# pixracer_serials.net
KiCad netlist of a schematic drawn in Altium Designer
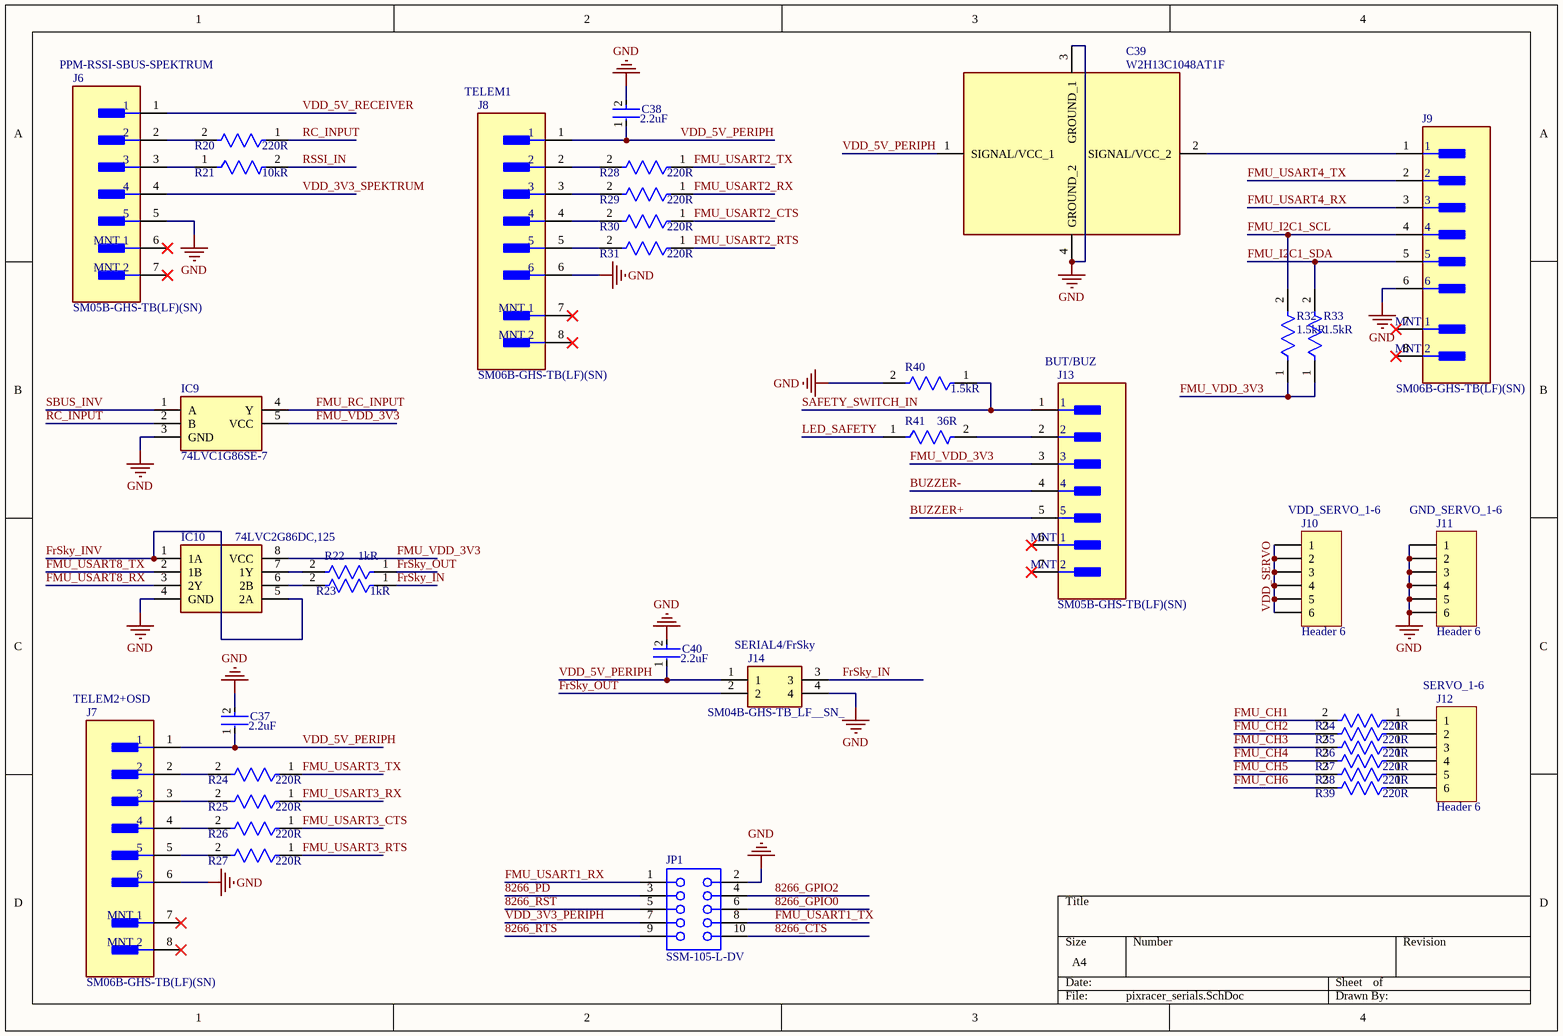
[diagram p0: pixracer_serials.SchDoc]

(export (version "E")
  (design (tool "Eeschema 10.0.6"))
  (components
    (comp (ref "C37")
      (value "C1608X7R1A225K080AC")
      (footprint "FP-C1608-080-0_1-MFG")
      (description "Multilayer Ceramic Capacitors 2.2μF ±10% 10V X7R SMD 0603")
      (fields (field (name "CAPACITANCE") "2.2uF") (field (name "TOLERANCE") "10%"))
      (libsource (lib "Altium Content Vault") (part "236180d848d6139a670b325ea6854c9"))
    )
    (comp (ref "C38")
      (value "C1608X7R1A225K080AC")
      (footprint "FP-C1608-080-0_1-MFG")
      (description "Multilayer Ceramic Capacitors 2.2μF ±10% 10V X7R SMD 0603")
      (fields (field (name "CAPACITANCE") "2.2uF") (field (name "TOLERANCE") "10%"))
      (libsource (lib "Altium Content Vault") (part "236180d848d6139a670b325ea6854c9"))
    )
    (comp (ref "C39")
      (value "W2H13C1048AT1F")
      (footprint "SamacSys:W2H13C1048AT1A")
      (description "Capacitor")
      (fields (field (name "MOUSER PART NUMBER") "581-W2H13C1048AT1F"))
      (libsource (lib "*") (part "W2H13C1048AT1F"))
    )
    (comp (ref "C40")
      (value "C1608X7R1A225K080AC")
      (footprint "FP-C1608-080-0_1-MFG")
      (description "Multilayer Ceramic Capacitors 2.2μF ±10% 10V X7R SMD 0603")
      (fields (field (name "CAPACITANCE") "2.2uF") (field (name "TOLERANCE") "10%"))
      (libsource (lib "Altium Content Vault") (part "236180d848d6139a670b325ea6854c9"))
    )
    (comp (ref "IC9")
      (value "74LVC1G86SE-7")
      (footprint "SamacSys:SOT65P210X110-5N")
      (description "Integrated Circuit")
      (fields (field (name "MOUSER PART NUMBER") "621-74LVC1G86SE-7"))
      (libsource (lib "*") (part "74LVC1G86SE-7"))
    )
    (comp (ref "IC10")
      (value "74LVC2G86DC,125")
      (footprint "SamacSys:SOP50P310X100-8N")
      (description "Integrated Circuit")
      (fields (field (name "MOUSER PART NUMBER") "771-LVC2G86DC125"))
      (libsource (lib "*") (part "74LVC2G86DC,125"))
    )
    (comp (ref "J6")
      (value "SM05B-GHS-TB(LF)(SN)")
      (footprint "FP-SM05B-GHS-TB_LF_SN-MFG")
      (description "CONN HEADER SMD R/A 5POS 1.25MM")
      (libsource (lib "Altium Content Vault") (part "8ab9848ea90b119fa28a5ddc5abf419"))
    )
    (comp (ref "J7")
      (value "SM06B-GHS-TB(LF)(SN)")
      (footprint "FP-SM06B-GHS-TB_LF_SN-MFG")
      (description "CONN HEADER SMD R/A 6POS 1.25MM")
      (libsource (lib "Altium Content Vault") (part "ed24c53d9ba001d1a2a686240a95171"))
    )
    (comp (ref "J8")
      (value "SM06B-GHS-TB(LF)(SN)")
      (footprint "FP-SM06B-GHS-TB_LF_SN-MFG")
      (description "CONN HEADER SMD R/A 6POS 1.25MM")
      (libsource (lib "Altium Content Vault") (part "ed24c53d9ba001d1a2a686240a95171"))
    )
    (comp (ref "J9")
      (value "SM06B-GHS-TB(LF)(SN)")
      (footprint "FP-SM06B-GHS-TB_LF_SN-MFG")
      (description "CONN HEADER SMD R/A 6POS 1.25MM")
      (libsource (lib "") (part "ed24c53d9ba001d1a2a686240a95171_1"))
    )
    (comp (ref "J10")
      (value "Header 6")
      (footprint "HDR1X6")
      (description "Header, 6-Pin")
      (fields (field (name "PUBLISHER") "Altium Limited"))
      (libsource (lib "Miscellaneous Connectors") (part "Header 6"))
    )
    (comp (ref "J11")
      (value "Header 6")
      (footprint "HDR1X6")
      (description "Header, 6-Pin")
      (fields (field (name "PUBLISHER") "Altium Limited"))
      (libsource (lib "Miscellaneous Connectors") (part "Header 6"))
    )
    (comp (ref "J12")
      (value "Header 6")
      (footprint "HDR1X6")
      (description "Header, 6-Pin")
      (fields (field (name "PUBLISHER") "Altium Limited"))
      (libsource (lib "Miscellaneous Connectors") (part "Header 6"))
    )
    (comp (ref "J13")
      (value "SM05B-GHS-TB(LF)(SN)")
      (footprint "FP-SM05B-GHS-TB_LF_SN-MFG")
      (description "CONN HEADER SMD R/A 5POS 1.25MM")
      (libsource (lib "") (part "8ab9848ea90b119fa28a5ddc5abf419_1"))
    )
    (comp (ref "J14")
      (value "SM04B-GHS-TB_LF__SN_")
      (footprint "SamacSys:SM04B-GHS-TB")
      (description "Connector")
      (fields (field (name "MANUFACTURER_PART_NUMBER") "SM04B-GHS-TB(LF)(SN)"))
      (libsource (lib "*") (part "SM04B-GHS-TB_LF__SN_"))
    )
    (comp (ref "JP1")
      (value "SSM-105-L-DV")
      (footprint "SMTC-SSM-105-X-DV")
      (fields (field (name "MANUFACTURER") "Samtec"))
      (libsource (lib "Altium Content Vault") (part "SMTC-SSM-105-X-DV"))
    )
    (comp (ref "R20")
      (value "CRCW0603220RFKEB")
      (footprint "FP-CRCW0603-e3-MFG")
      (description "RES Thick Film, 220Ω, 1%, 0.1W, 100ppm/°C, 0603")
      (fields (field (name "TOLERANCE") "1%") (field (name "RESISTANCE") "220R"))
      (libsource (lib "Altium Content Vault") (part "1029c3af85768c4190bb7ad29bc67b5"))
    )
    (comp (ref "R21")
      (value "ERJ-3GEYJ103V")
      (footprint "FP-ERJ3G-IPC_C")
      (description "RES SMD 10K OHM 5% 1/10W 0603")
      (fields (field (name "TOLERANCE") "5%") (field (name "RESISTANCE") "10kR"))
      (libsource (lib "Altium Content Vault") (part "1029c3af85768c4190bb7ad29bc67b5"))
    )
    (comp (ref "R22")
      (value "RC1608J102CS")
      (footprint "FP-RC1608-IPC_A")
      (description "Res Thick Film 0603 1kΩ 5% 0.1W ±100ppm/°C Molded SMD T/R")
      (fields (field (name "RESISTANCE") "1kR") (field (name "TOLERANCE") "5%"))
      (libsource (lib "Altium Content Vault") (part "1029c3af85768c4190bb7ad29bc67b5"))
    )
    (comp (ref "R23")
      (value "RC1608J102CS")
      (footprint "FP-RC1608-IPC_A")
      (description "Res Thick Film 0603 1kΩ 5% 0.1W ±100ppm/°C Molded SMD T/R")
      (fields (field (name "RESISTANCE") "1kR") (field (name "TOLERANCE") "5%"))
      (libsource (lib "Altium Content Vault") (part "1029c3af85768c4190bb7ad29bc67b5"))
    )
    (comp (ref "R24")
      (value "CRCW0603220RFKEB")
      (footprint "FP-CRCW0603-e3-MFG")
      (description "RES Thick Film, 220Ω, 1%, 0.1W, 100ppm/°C, 0603")
      (fields (field (name "TOLERANCE") "1%") (field (name "RESISTANCE") "220R"))
      (libsource (lib "Altium Content Vault") (part "1029c3af85768c4190bb7ad29bc67b5"))
    )
    (comp (ref "R25")
      (value "CRCW0603220RFKEB")
      (footprint "FP-CRCW0603-e3-MFG")
      (description "RES Thick Film, 220Ω, 1%, 0.1W, 100ppm/°C, 0603")
      (fields (field (name "TOLERANCE") "1%") (field (name "RESISTANCE") "220R"))
      (libsource (lib "Altium Content Vault") (part "1029c3af85768c4190bb7ad29bc67b5"))
    )
    (comp (ref "R26")
      (value "CRCW0603220RFKEB")
      (footprint "FP-CRCW0603-e3-MFG")
      (description "RES Thick Film, 220Ω, 1%, 0.1W, 100ppm/°C, 0603")
      (fields (field (name "TOLERANCE") "1%") (field (name "RESISTANCE") "220R"))
      (libsource (lib "Altium Content Vault") (part "1029c3af85768c4190bb7ad29bc67b5"))
    )
    (comp (ref "R27")
      (value "CRCW0603220RFKEB")
      (footprint "FP-CRCW0603-e3-MFG")
      (description "RES Thick Film, 220Ω, 1%, 0.1W, 100ppm/°C, 0603")
      (fields (field (name "TOLERANCE") "1%") (field (name "RESISTANCE") "220R"))
      (libsource (lib "Altium Content Vault") (part "1029c3af85768c4190bb7ad29bc67b5"))
    )
    (comp (ref "R28")
      (value "CRCW0603220RFKEB")
      (footprint "FP-CRCW0603-e3-MFG")
      (description "RES Thick Film, 220Ω, 1%, 0.1W, 100ppm/°C, 0603")
      (fields (field (name "TOLERANCE") "1%") (field (name "RESISTANCE") "220R"))
      (libsource (lib "Altium Content Vault") (part "1029c3af85768c4190bb7ad29bc67b5"))
    )
    (comp (ref "R29")
      (value "CRCW0603220RFKEB")
      (footprint "FP-CRCW0603-e3-MFG")
      (description "RES Thick Film, 220Ω, 1%, 0.1W, 100ppm/°C, 0603")
      (fields (field (name "TOLERANCE") "1%") (field (name "RESISTANCE") "220R"))
      (libsource (lib "Altium Content Vault") (part "1029c3af85768c4190bb7ad29bc67b5"))
    )
    (comp (ref "R30")
      (value "CRCW0603220RFKEB")
      (footprint "FP-CRCW0603-e3-MFG")
      (description "RES Thick Film, 220Ω, 1%, 0.1W, 100ppm/°C, 0603")
      (fields (field (name "TOLERANCE") "1%") (field (name "RESISTANCE") "220R"))
      (libsource (lib "Altium Content Vault") (part "1029c3af85768c4190bb7ad29bc67b5"))
    )
    (comp (ref "R31")
      (value "CRCW0603220RFKEB")
      (footprint "FP-CRCW0603-e3-MFG")
      (description "RES Thick Film, 220Ω, 1%, 0.1W, 100ppm/°C, 0603")
      (fields (field (name "TOLERANCE") "1%") (field (name "RESISTANCE") "220R"))
      (libsource (lib "Altium Content Vault") (part "1029c3af85768c4190bb7ad29bc67b5"))
    )
    (comp (ref "R32")
      (value "1.5kR")
      (footprint "FP-CPF0603-MFG")
      (description "RES SMD 1.5KΩ 0.1% 1/16W 0603")
      (fields
        (field (name "MANUFACTURER PART NUMBER") "CPF0603B1K5E1")
        (field (name "OCTOPART") "https://octopart.com/cpf0603b1k5e1-te+connectivity-9539421")
      )
      (libsource (lib "Altium Content Vault") (part "1029c3af85768c4190bb7ad29bc67b5"))
    )
    (comp (ref "R33")
      (value "1.5kR")
      (footprint "FP-CPF0603-MFG")
      (description "RES SMD 1.5KΩ 0.1% 1/16W 0603")
      (fields
        (field (name "MANUFACTURER PART NUMBER") "CPF0603B1K5E1")
        (field (name "OCTOPART") "https://octopart.com/cpf0603b1k5e1-te+connectivity-9539421")
      )
      (libsource (lib "Altium Content Vault") (part "1029c3af85768c4190bb7ad29bc67b5"))
    )
    (comp (ref "R34")
      (value "CRCW0603220RFKEB")
      (footprint "FP-CRCW0603-e3-MFG")
      (description "RES Thick Film, 220Ω, 1%, 0.1W, 100ppm/°C, 0603")
      (fields (field (name "TOLERANCE") "1%") (field (name "RESISTANCE") "220R"))
      (libsource (lib "Altium Content Vault") (part "1029c3af85768c4190bb7ad29bc67b5"))
    )
    (comp (ref "R35")
      (value "CRCW0603220RFKEB")
      (footprint "FP-CRCW0603-e3-MFG")
      (description "RES Thick Film, 220Ω, 1%, 0.1W, 100ppm/°C, 0603")
      (fields (field (name "TOLERANCE") "1%") (field (name "RESISTANCE") "220R"))
      (libsource (lib "Altium Content Vault") (part "1029c3af85768c4190bb7ad29bc67b5"))
    )
    (comp (ref "R36")
      (value "CRCW0603220RFKEB")
      (footprint "FP-CRCW0603-e3-MFG")
      (description "RES Thick Film, 220Ω, 1%, 0.1W, 100ppm/°C, 0603")
      (fields (field (name "TOLERANCE") "1%") (field (name "RESISTANCE") "220R"))
      (libsource (lib "Altium Content Vault") (part "1029c3af85768c4190bb7ad29bc67b5"))
    )
    (comp (ref "R37")
      (value "CRCW0603220RFKEB")
      (footprint "FP-CRCW0603-e3-MFG")
      (description "RES Thick Film, 220Ω, 1%, 0.1W, 100ppm/°C, 0603")
      (fields (field (name "TOLERANCE") "1%") (field (name "RESISTANCE") "220R"))
      (libsource (lib "Altium Content Vault") (part "1029c3af85768c4190bb7ad29bc67b5"))
    )
    (comp (ref "R38")
      (value "CRCW0603220RFKEB")
      (footprint "FP-CRCW0603-e3-MFG")
      (description "RES Thick Film, 220Ω, 1%, 0.1W, 100ppm/°C, 0603")
      (fields (field (name "TOLERANCE") "1%") (field (name "RESISTANCE") "220R"))
      (libsource (lib "Altium Content Vault") (part "1029c3af85768c4190bb7ad29bc67b5"))
    )
    (comp (ref "R39")
      (value "CRCW0603220RFKEB")
      (footprint "FP-CRCW0603-e3-MFG")
      (description "RES Thick Film, 220Ω, 1%, 0.1W, 100ppm/°C, 0603")
      (fields (field (name "TOLERANCE") "1%") (field (name "RESISTANCE") "220R"))
      (libsource (lib "Altium Content Vault") (part "1029c3af85768c4190bb7ad29bc67b5"))
    )
    (comp (ref "R40")
      (value "MCR03EZPFX1501")
      (footprint "FP-MCR03-IPC_A")
      (description "Thick Film Chip Resistor, 0603, 1.5kΩ, 1%, 100ppm/°C, 0.1W, 50V")
      (fields (field (name "RESISTANCE") "1.5kR") (field (name "TOLERANCE") "1%"))
      (libsource (lib "Altium Content Vault") (part "1029c3af85768c4190bb7ad29bc67b5"))
    )
    (comp (ref "R41")
      (value "CRCW060336R0JNEA")
      (footprint "FP-CRCW0603-e3-IPC_B")
      (description "RES Thick Film, 36Ω, 5%, 0.1W, 200ppm/°C, 0603")
      (fields (field (name "RESISTANCE") "36R") (field (name "TOLERANCE") "5%"))
      (libsource (lib "Altium Content Vault") (part "1029c3af85768c4190bb7ad29bc67b5"))
    )
  )
  (nets
    (net (code "1") (name "/8266_CTS") (class "Default")
      (node (ref "JP1") (pin "10") (pinfunction "10_10") (pintype "passive"))
    )
    (net (code "2") (name "/8266_GPIO0") (class "Default")
      (node (ref "JP1") (pin "6") (pinfunction "6_6") (pintype "passive"))
    )
    (net (code "3") (name "/8266_GPIO2") (class "Default")
      (node (ref "JP1") (pin "4") (pinfunction "4_4") (pintype "passive"))
    )
    (net (code "4") (name "/8266_PD") (class "Default")
      (node (ref "JP1") (pin "3") (pinfunction "3_3") (pintype "passive"))
    )
    (net (code "5") (name "/8266_RST") (class "Default")
      (node (ref "JP1") (pin "5") (pinfunction "5_5") (pintype "passive"))
    )
    (net (code "6") (name "/8266_RTS") (class "Default")
      (node (ref "JP1") (pin "9") (pinfunction "9_9") (pintype "passive"))
    )
    (net (code "7") (name "/BUZZER+") (class "Default")
      (node (ref "J13") (pin "5") (pinfunction "5_5") (pintype "passive"))
    )
    (net (code "8") (name "/BUZZER-") (class "Default")
      (node (ref "J13") (pin "4") (pinfunction "4_4") (pintype "passive"))
    )
    (net (code "9") (name "/FMU_CH1") (class "Default")
      (node (ref "R34") (pin "2") (pinfunction "2_2") (pintype "passive"))
    )
    (net (code "10") (name "/FMU_CH2") (class "Default")
      (node (ref "R35") (pin "2") (pinfunction "2_2") (pintype "passive"))
    )
    (net (code "11") (name "/FMU_CH3") (class "Default")
      (node (ref "R36") (pin "2") (pinfunction "2_2") (pintype "passive"))
    )
    (net (code "12") (name "/FMU_CH4") (class "Default")
      (node (ref "R37") (pin "2") (pinfunction "2_2") (pintype "passive"))
    )
    (net (code "13") (name "/FMU_CH5") (class "Default")
      (node (ref "R38") (pin "2") (pinfunction "2_2") (pintype "passive"))
    )
    (net (code "14") (name "/FMU_CH6") (class "Default")
      (node (ref "R39") (pin "2") (pinfunction "2_2") (pintype "passive"))
    )
    (net (code "15") (name "/FMU_I2C1_SCL") (class "Default")
      (node (ref "J9") (pin "4") (pinfunction "4_4") (pintype "passive"))
      (node (ref "R32") (pin "2") (pinfunction "2_2") (pintype "passive"))
    )
    (net (code "16") (name "/FMU_I2C1_SDA") (class "Default")
      (node (ref "J9") (pin "5") (pinfunction "5_5") (pintype "passive"))
      (node (ref "R33") (pin "2") (pinfunction "2_2") (pintype "passive"))
    )
    (net (code "17") (name "/FMU_RC_INPUT") (class "Default")
      (node (ref "IC9") (pin "4") (pinfunction "Y_4") (pintype "passive"))
    )
    (net (code "18") (name "/FMU_USART1_RX") (class "Default")
      (node (ref "JP1") (pin "1") (pinfunction "1_1") (pintype "passive"))
    )
    (net (code "19") (name "/FMU_USART1_TX") (class "Default")
      (node (ref "JP1") (pin "8") (pinfunction "8_8") (pintype "passive"))
    )
    (net (code "20") (name "/FMU_USART2_CTS") (class "Default")
      (node (ref "R30") (pin "1") (pinfunction "1_1") (pintype "passive"))
    )
    (net (code "21") (name "/FMU_USART2_RTS") (class "Default")
      (node (ref "R31") (pin "1") (pinfunction "1_1") (pintype "passive"))
    )
    (net (code "22") (name "/FMU_USART2_RX") (class "Default")
      (node (ref "R29") (pin "1") (pinfunction "1_1") (pintype "passive"))
    )
    (net (code "23") (name "/FMU_USART2_TX") (class "Default")
      (node (ref "R28") (pin "1") (pinfunction "1_1") (pintype "passive"))
    )
    (net (code "24") (name "/FMU_USART3_CTS") (class "Default")
      (node (ref "R26") (pin "1") (pinfunction "1_1") (pintype "passive"))
    )
    (net (code "25") (name "/FMU_USART3_RTS") (class "Default")
      (node (ref "R27") (pin "1") (pinfunction "1_1") (pintype "passive"))
    )
    (net (code "26") (name "/FMU_USART3_RX") (class "Default")
      (node (ref "R25") (pin "1") (pinfunction "1_1") (pintype "passive"))
    )
    (net (code "27") (name "/FMU_USART3_TX") (class "Default")
      (node (ref "R24") (pin "1") (pinfunction "1_1") (pintype "passive"))
    )
    (net (code "28") (name "/FMU_USART4_RX") (class "Default")
      (node (ref "J9") (pin "3") (pinfunction "3_3") (pintype "passive"))
    )
    (net (code "29") (name "/FMU_USART4_TX") (class "Default")
      (node (ref "J9") (pin "2") (pinfunction "2_2") (pintype "passive"))
    )
    (net (code "30") (name "/FMU_USART8_RX") (class "Default")
      (node (ref "IC10") (pin "3") (pinfunction "2Y_3") (pintype "passive"))
    )
    (net (code "31") (name "/FMU_USART8_TX") (class "Default")
      (node (ref "IC10") (pin "2") (pinfunction "1B_2") (pintype "passive"))
    )
    (net (code "32") (name "/FMU_VDD_3V3") (class "Default")
      (node (ref "IC10") (pin "8") (pinfunction "VCC_8") (pintype "passive"))
      (node (ref "IC9") (pin "5") (pinfunction "VCC_5") (pintype "passive"))
      (node (ref "J13") (pin "3") (pinfunction "3_3") (pintype "passive"))
      (node (ref "R32") (pin "1") (pinfunction "1_1") (pintype "passive"))
      (node (ref "R33") (pin "1") (pinfunction "1_1") (pintype "passive"))
    )
    (net (code "33") (name "/FrSky_IN") (class "Default")
      (node (ref "J14") (pin "3") (pinfunction "3_3") (pintype "passive"))
      (node (ref "R23") (pin "1") (pinfunction "1_1") (pintype "passive"))
    )
    (net (code "34") (name "/FrSky_INV") (class "Default")
      (node (ref "IC10") (pin "1") (pinfunction "1A_1") (pintype "passive"))
      (node (ref "IC10") (pin "5") (pinfunction "2A_5") (pintype "passive"))
    )
    (net (code "35") (name "/FrSky_OUT") (class "Default")
      (node (ref "J14") (pin "2") (pinfunction "2_2") (pintype "passive"))
      (node (ref "R22") (pin "1") (pinfunction "1_1") (pintype "passive"))
    )
    (net (code "36") (name "/LED_SAFETY") (class "Default")
      (node (ref "R41") (pin "1") (pinfunction "1_1") (pintype "passive"))
    )
    (net (code "37") (name "/RC_INPUT") (class "Default")
      (node (ref "IC9") (pin "2") (pinfunction "B_2") (pintype "passive"))
      (node (ref "R20") (pin "1") (pinfunction "1_1") (pintype "passive"))
    )
    (net (code "38") (name "/RSSI_IN") (class "Default")
      (node (ref "R21") (pin "2") (pinfunction "2_2") (pintype "passive"))
    )
    (net (code "39") (name "/SAFETY_SWITCH_IN") (class "Default")
      (node (ref "J13") (pin "1") (pinfunction "1_1") (pintype "passive"))
      (node (ref "R40") (pin "1") (pinfunction "1_1") (pintype "passive"))
    )
    (net (code "40") (name "/SBUS_INV") (class "Default")
      (node (ref "IC9") (pin "1") (pinfunction "A_1") (pintype "passive"))
    )
    (net (code "41") (name "/VDD_3V3_PERIPH") (class "Default")
      (node (ref "JP1") (pin "7") (pinfunction "7_7") (pintype "passive"))
    )
    (net (code "42") (name "/VDD_3V3_SPEKTRUM") (class "Default")
      (node (ref "J6") (pin "4") (pinfunction "4_4") (pintype "passive"))
    )
    (net (code "43") (name "/VDD_5V_PERIPH") (class "Default")
      (node (ref "C37") (pin "1") (pinfunction "1_1") (pintype "passive"))
      (node (ref "C38") (pin "1") (pinfunction "1_1") (pintype "passive"))
      (node (ref "C39") (pin "1") (pinfunction "SIGNAL/VCC_1_1") (pintype "passive"))
      (node (ref "C40") (pin "1") (pinfunction "1_1") (pintype "passive"))
      (node (ref "J14") (pin "1") (pinfunction "1_1") (pintype "passive"))
      (node (ref "J7") (pin "1") (pinfunction "1_1") (pintype "passive"))
      (node (ref "J8") (pin "1") (pinfunction "1_1") (pintype "passive"))
    )
    (net (code "44") (name "/VDD_5V_RECEIVER") (class "Default")
      (node (ref "J6") (pin "1") (pinfunction "1_1") (pintype "passive"))
    )
    (net (code "45") (name "/VDD_SERVO") (class "Default")
      (node (ref "J10") (pin "1") (pinfunction "1_1") (pintype "passive"))
      (node (ref "J10") (pin "2") (pinfunction "2_2") (pintype "passive"))
      (node (ref "J10") (pin "3") (pinfunction "3_3") (pintype "passive"))
      (node (ref "J10") (pin "4") (pinfunction "4_4") (pintype "passive"))
      (node (ref "J10") (pin "5") (pinfunction "5_5") (pintype "passive"))
      (node (ref "J10") (pin "6") (pinfunction "6_6") (pintype "passive"))
    )
    (net (code "46") (name "GND") (class "Default")
      (node (ref "C37") (pin "2") (pinfunction "2_2") (pintype "passive"))
      (node (ref "C38") (pin "2") (pinfunction "2_2") (pintype "passive"))
      (node (ref "C39") (pin "3") (pinfunction "GROUND_1_3") (pintype "passive"))
      (node (ref "C39") (pin "4") (pinfunction "GROUND_2_4") (pintype "passive"))
      (node (ref "C40") (pin "2") (pinfunction "2_2") (pintype "passive"))
      (node (ref "IC10") (pin "4") (pinfunction "GND_4") (pintype "passive"))
      (node (ref "IC9") (pin "3") (pinfunction "GND_3") (pintype "passive"))
      (node (ref "J11") (pin "1") (pinfunction "1_1") (pintype "passive"))
      (node (ref "J11") (pin "2") (pinfunction "2_2") (pintype "passive"))
      (node (ref "J11") (pin "3") (pinfunction "3_3") (pintype "passive"))
      (node (ref "J11") (pin "4") (pinfunction "4_4") (pintype "passive"))
      (node (ref "J11") (pin "5") (pinfunction "5_5") (pintype "passive"))
      (node (ref "J11") (pin "6") (pinfunction "6_6") (pintype "passive"))
      (node (ref "J14") (pin "4") (pinfunction "4_4") (pintype "passive"))
      (node (ref "J6") (pin "5") (pinfunction "5_5") (pintype "passive"))
      (node (ref "J7") (pin "6") (pinfunction "6_6") (pintype "passive"))
      (node (ref "J8") (pin "6") (pinfunction "6_6") (pintype "passive"))
      (node (ref "J9") (pin "6") (pinfunction "6_6") (pintype "passive"))
      (node (ref "JP1") (pin "2") (pinfunction "2_2") (pintype "passive"))
      (node (ref "R40") (pin "2") (pinfunction "2_2") (pintype "passive"))
    )
    (net (code "47") (name "Net-(C39-SIGNAL{slash}VCC_2)") (class "Default")
      (node (ref "C39") (pin "2") (pinfunction "SIGNAL/VCC_2_2") (pintype "passive"))
      (node (ref "J9") (pin "1") (pinfunction "1_1") (pintype "passive"))
    )
    (net (code "48") (name "Net-(IC10-1Y)") (class "Default")
      (node (ref "IC10") (pin "7") (pinfunction "1Y_7") (pintype "passive"))
      (node (ref "R22") (pin "2") (pinfunction "2_2") (pintype "passive"))
    )
    (net (code "49") (name "Net-(IC10-2B)") (class "Default")
      (node (ref "IC10") (pin "6") (pinfunction "2B_6") (pintype "passive"))
      (node (ref "R23") (pin "2") (pinfunction "2_2") (pintype "passive"))
    )
    (net (code "50") (name "Net-(J6-Pad2)") (class "Default")
      (node (ref "J6") (pin "2") (pinfunction "2_2") (pintype "passive"))
      (node (ref "R20") (pin "2") (pinfunction "2_2") (pintype "passive"))
    )
    (net (code "51") (name "Net-(J6-Pad3)") (class "Default")
      (node (ref "J6") (pin "3") (pinfunction "3_3") (pintype "passive"))
      (node (ref "R21") (pin "1") (pinfunction "1_1") (pintype "passive"))
    )
    (net (code "52") (name "Net-(J7-Pad2)") (class "Default")
      (node (ref "J7") (pin "2") (pinfunction "2_2") (pintype "passive"))
      (node (ref "R24") (pin "2") (pinfunction "2_2") (pintype "passive"))
    )
    (net (code "53") (name "Net-(J7-Pad3)") (class "Default")
      (node (ref "J7") (pin "3") (pinfunction "3_3") (pintype "passive"))
      (node (ref "R25") (pin "2") (pinfunction "2_2") (pintype "passive"))
    )
    (net (code "54") (name "Net-(J7-Pad4)") (class "Default")
      (node (ref "J7") (pin "4") (pinfunction "4_4") (pintype "passive"))
      (node (ref "R26") (pin "2") (pinfunction "2_2") (pintype "passive"))
    )
    (net (code "55") (name "Net-(J7-Pad5)") (class "Default")
      (node (ref "J7") (pin "5") (pinfunction "5_5") (pintype "passive"))
      (node (ref "R27") (pin "2") (pinfunction "2_2") (pintype "passive"))
    )
    (net (code "56") (name "Net-(J8-Pad2)") (class "Default")
      (node (ref "J8") (pin "2") (pinfunction "2_2") (pintype "passive"))
      (node (ref "R28") (pin "2") (pinfunction "2_2") (pintype "passive"))
    )
    (net (code "57") (name "Net-(J8-Pad3)") (class "Default")
      (node (ref "J8") (pin "3") (pinfunction "3_3") (pintype "passive"))
      (node (ref "R29") (pin "2") (pinfunction "2_2") (pintype "passive"))
    )
    (net (code "58") (name "Net-(J8-Pad4)") (class "Default")
      (node (ref "J8") (pin "4") (pinfunction "4_4") (pintype "passive"))
      (node (ref "R30") (pin "2") (pinfunction "2_2") (pintype "passive"))
    )
    (net (code "59") (name "Net-(J8-Pad5)") (class "Default")
      (node (ref "J8") (pin "5") (pinfunction "5_5") (pintype "passive"))
      (node (ref "R31") (pin "2") (pinfunction "2_2") (pintype "passive"))
    )
    (net (code "60") (name "Net-(J12-Pad1)") (class "Default")
      (node (ref "J12") (pin "1") (pinfunction "1_1") (pintype "passive"))
      (node (ref "R34") (pin "1") (pinfunction "1_1") (pintype "passive"))
    )
    (net (code "61") (name "Net-(J12-Pad2)") (class "Default")
      (node (ref "J12") (pin "2") (pinfunction "2_2") (pintype "passive"))
      (node (ref "R35") (pin "1") (pinfunction "1_1") (pintype "passive"))
    )
    (net (code "62") (name "Net-(J12-Pad3)") (class "Default")
      (node (ref "J12") (pin "3") (pinfunction "3_3") (pintype "passive"))
      (node (ref "R36") (pin "1") (pinfunction "1_1") (pintype "passive"))
    )
    (net (code "63") (name "Net-(J12-Pad4)") (class "Default")
      (node (ref "J12") (pin "4") (pinfunction "4_4") (pintype "passive"))
      (node (ref "R37") (pin "1") (pinfunction "1_1") (pintype "passive"))
    )
    (net (code "64") (name "Net-(J12-Pad5)") (class "Default")
      (node (ref "J12") (pin "5") (pinfunction "5_5") (pintype "passive"))
      (node (ref "R38") (pin "1") (pinfunction "1_1") (pintype "passive"))
    )
    (net (code "65") (name "Net-(J12-Pad6)") (class "Default")
      (node (ref "J12") (pin "6") (pinfunction "6_6") (pintype "passive"))
      (node (ref "R39") (pin "1") (pinfunction "1_1") (pintype "passive"))
    )
    (net (code "66") (name "Net-(J13-Pad2)") (class "Default")
      (node (ref "J13") (pin "2") (pinfunction "2_2") (pintype "passive"))
      (node (ref "R41") (pin "2") (pinfunction "2_2") (pintype "passive"))
    )
    (net (code "67") (name "unconnected-(J6-MNT_1-Pad6)") (class "Default")
      (node (ref "J6") (pin "6") (pinfunction "MNT_1_6") (pintype "passive+no_connect"))
    )
    (net (code "68") (name "unconnected-(J6-MNT_2-Pad7)") (class "Default")
      (node (ref "J6") (pin "7") (pinfunction "MNT_2_7") (pintype "passive+no_connect"))
    )
    (net (code "69") (name "unconnected-(J7-MNT_1-Pad7)") (class "Default")
      (node (ref "J7") (pin "7") (pinfunction "MNT_1_7") (pintype "passive+no_connect"))
    )
    (net (code "70") (name "unconnected-(J7-MNT_2-Pad8)") (class "Default")
      (node (ref "J7") (pin "8") (pinfunction "MNT_2_8") (pintype "passive+no_connect"))
    )
    (net (code "71") (name "unconnected-(J8-MNT_1-Pad7)") (class "Default")
      (node (ref "J8") (pin "7") (pinfunction "MNT_1_7") (pintype "passive+no_connect"))
    )
    (net (code "72") (name "unconnected-(J8-MNT_2-Pad8)") (class "Default")
      (node (ref "J8") (pin "8") (pinfunction "MNT_2_8") (pintype "passive+no_connect"))
    )
    (net (code "73") (name "unconnected-(J9-MNT_1-Pad7)") (class "Default")
      (node (ref "J9") (pin "7") (pinfunction "MNT_1_7") (pintype "passive+no_connect"))
    )
    (net (code "74") (name "unconnected-(J9-MNT_2-Pad8)") (class "Default")
      (node (ref "J9") (pin "8") (pinfunction "MNT_2_8") (pintype "passive+no_connect"))
    )
    (net (code "75") (name "unconnected-(J13-MNT_1-Pad6)") (class "Default")
      (node (ref "J13") (pin "6") (pinfunction "MNT_1_6") (pintype "passive+no_connect"))
    )
    (net (code "76") (name "unconnected-(J13-MNT_2-Pad7)") (class "Default")
      (node (ref "J13") (pin "7") (pinfunction "MNT_2_7") (pintype "passive+no_connect"))
    )
  )
)
